# Backplane-4.net
KiCad netlist of a schematic drawn in EAGLE
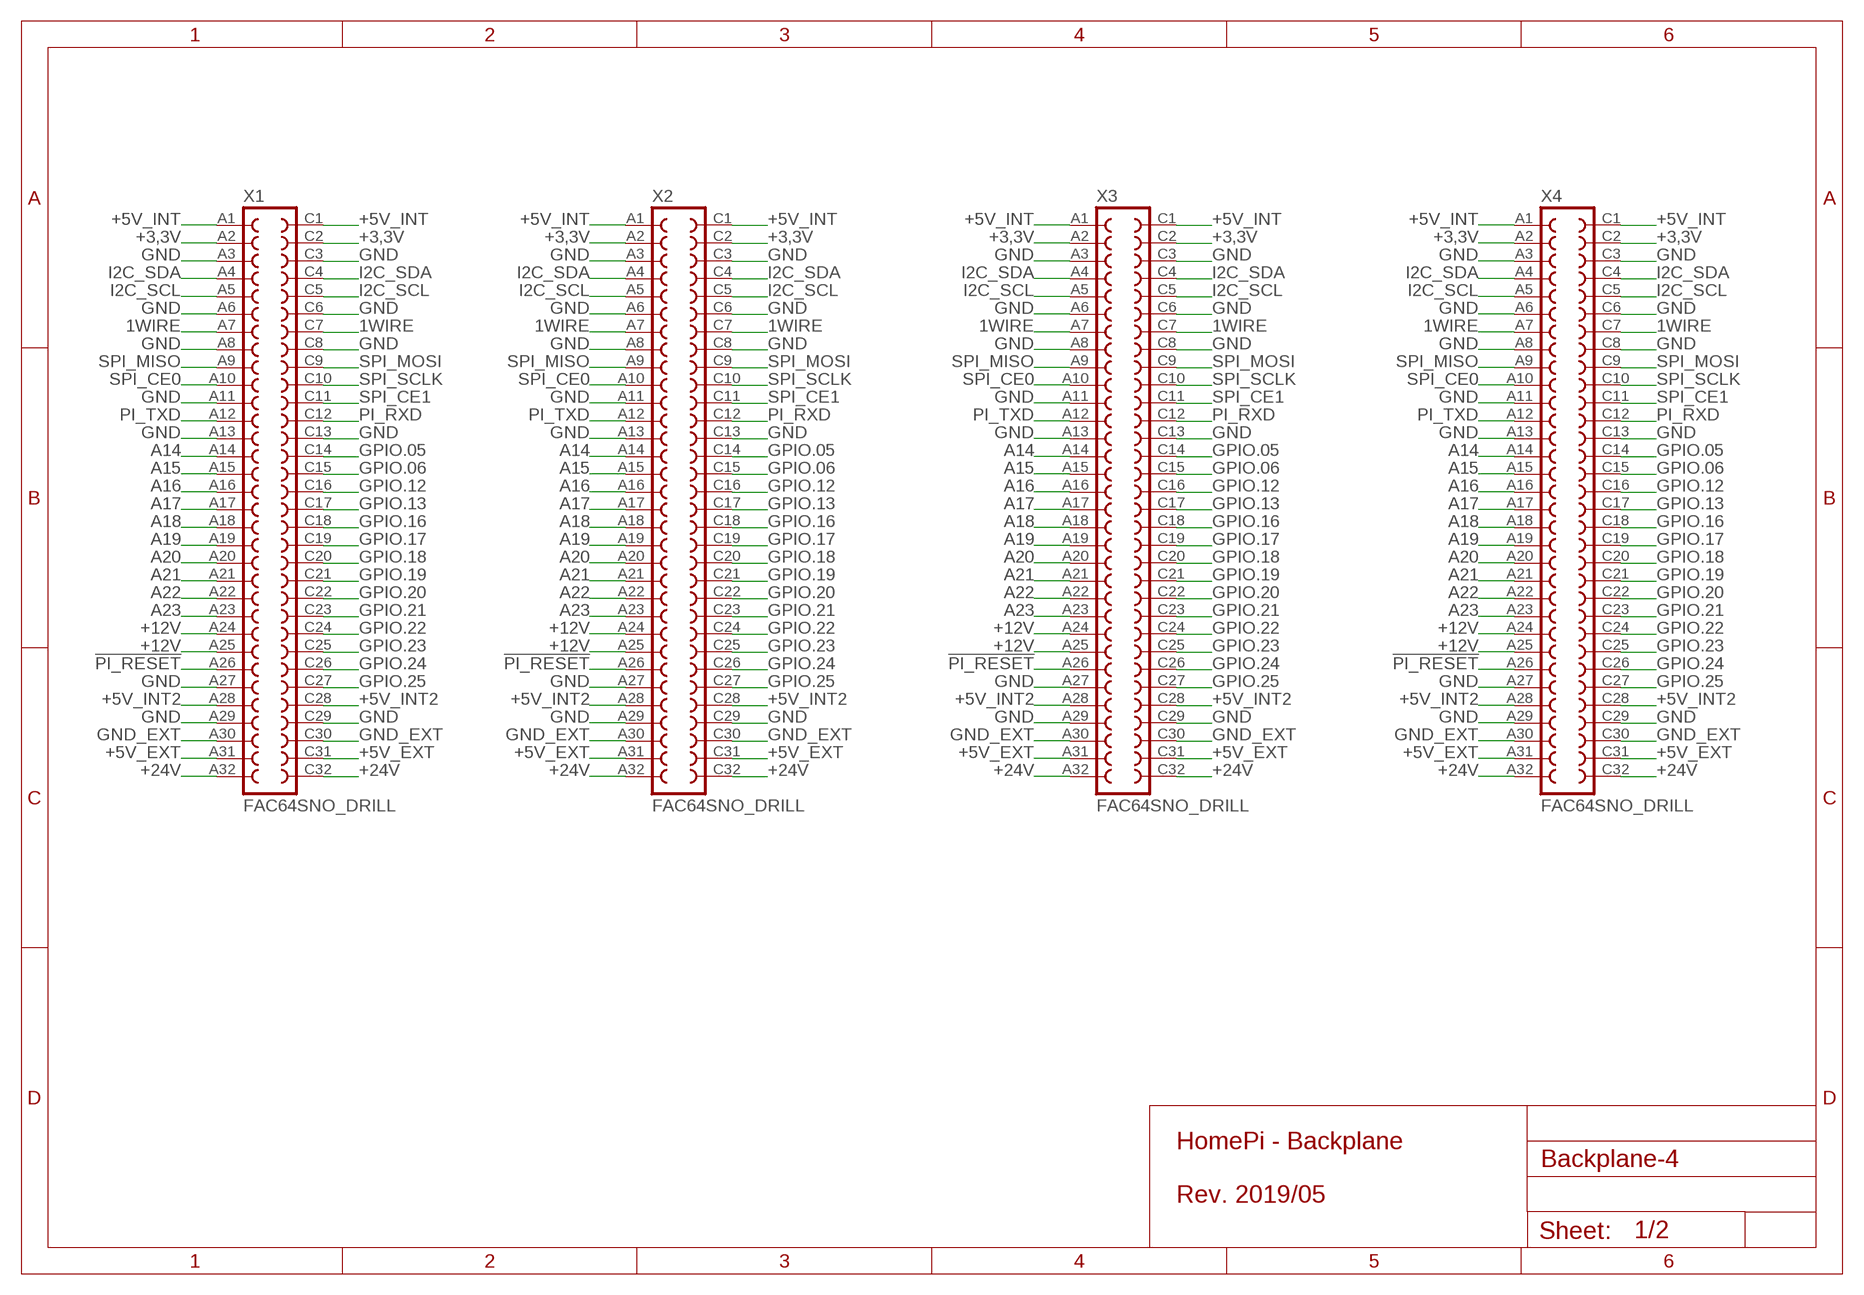
[diagram p0: schematic, sheet 1]
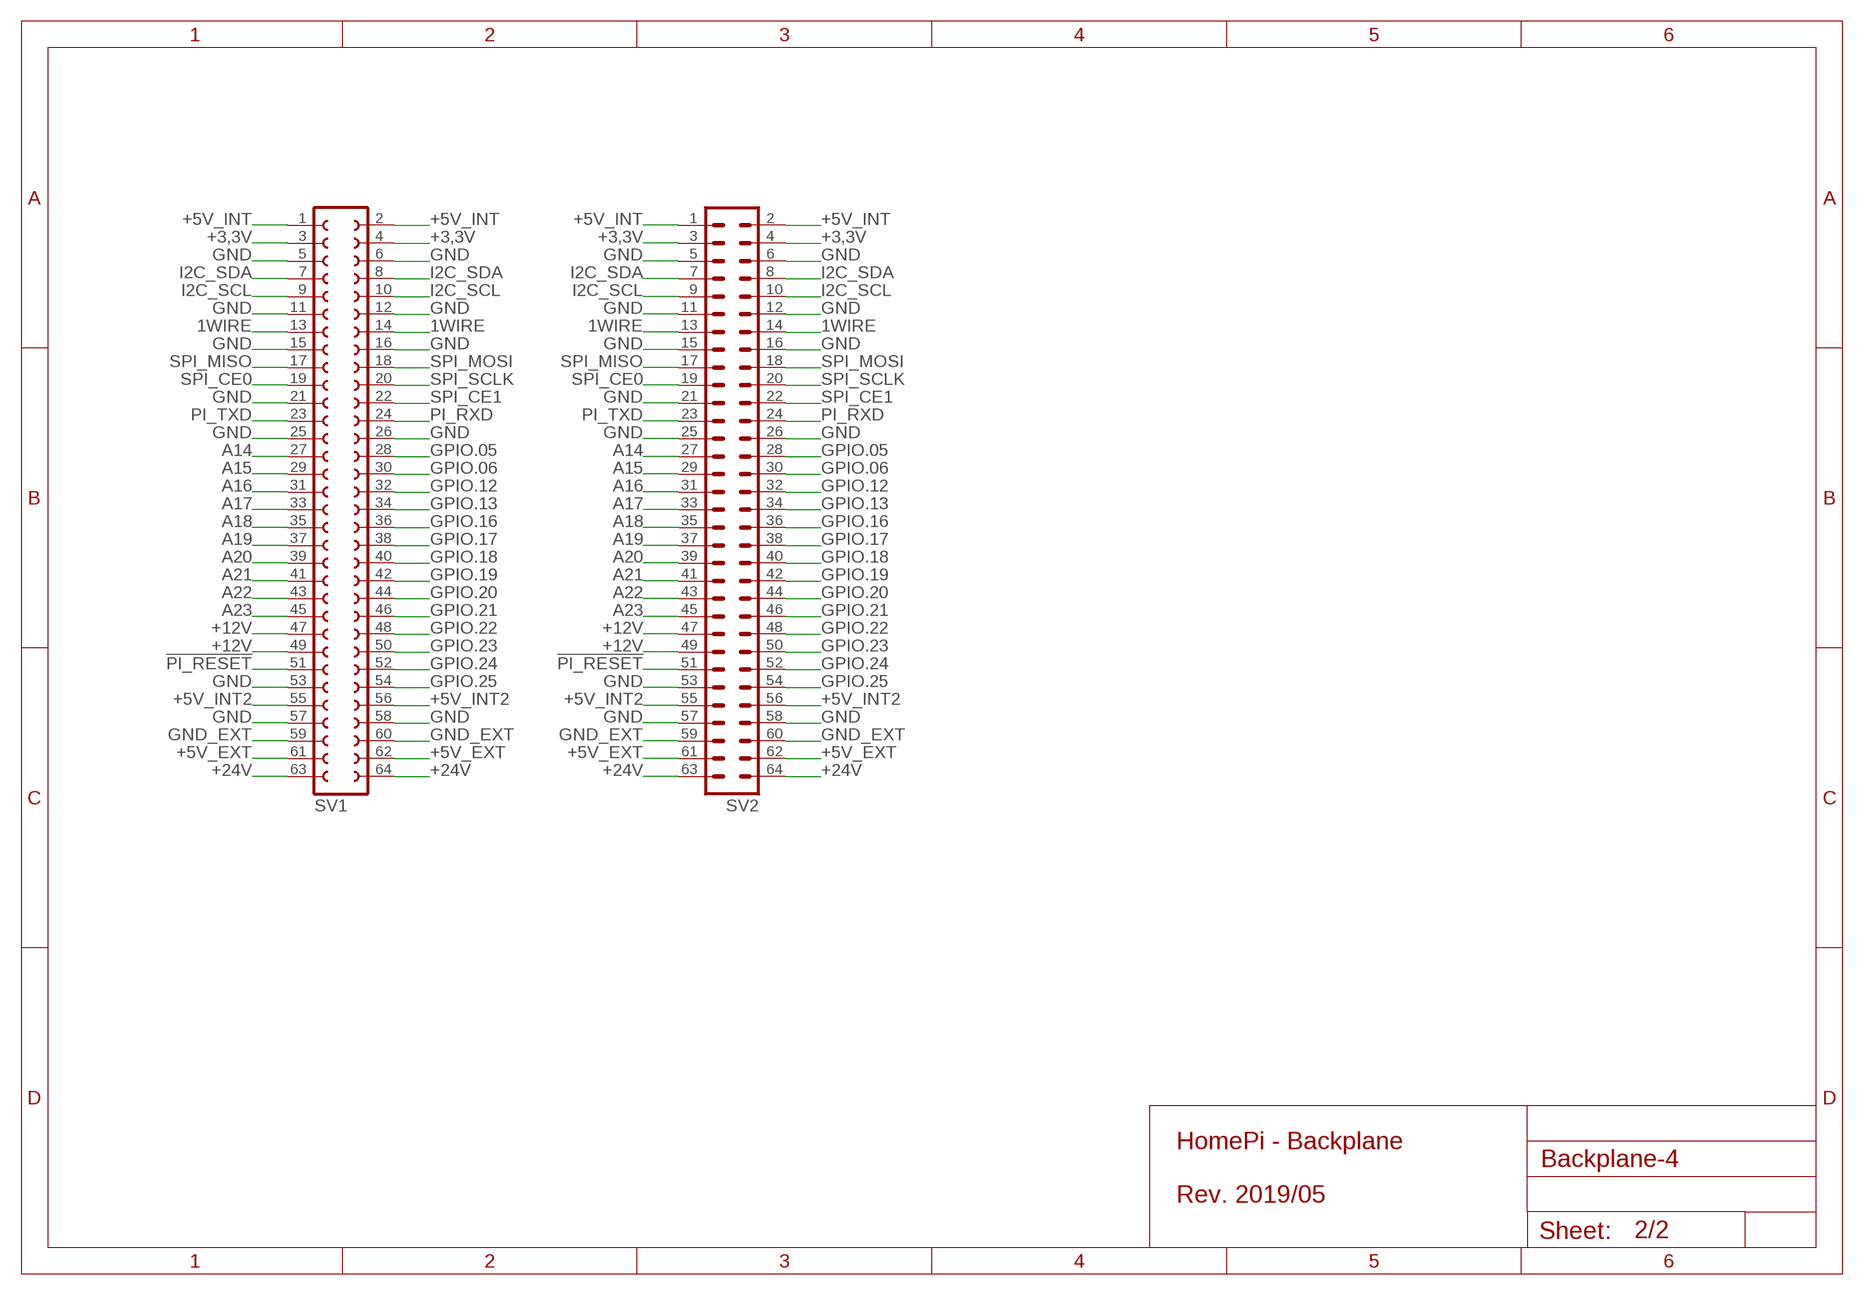
[diagram p1: schematic, sheet 2]

(export (version "E")
  (design (tool "Eeschema 10.0.6"))
  (components
    (comp (ref "X1")
      (value "FAC64SNO_DRILL")
      (footprint "eagle-import:FAC64S_NO_DRILL")
      (libsource (lib "eagle-import") (part "FAC64SNO_DRILL"))
    )
    (comp (ref "X2")
      (value "FAC64SNO_DRILL")
      (footprint "eagle-import:FAC64S_NO_DRILL")
      (libsource (lib "eagle-import") (part "FAC64SNO_DRILL"))
    )
    (comp (ref "X3")
      (value "FAC64SNO_DRILL")
      (footprint "eagle-import:FAC64S_NO_DRILL")
      (libsource (lib "eagle-import") (part "FAC64SNO_DRILL"))
    )
    (comp (ref "X4")
      (value "FAC64SNO_DRILL")
      (footprint "eagle-import:FAC64S_NO_DRILL")
      (libsource (lib "eagle-import") (part "FAC64SNO_DRILL"))
    )
    (comp (ref "SV1")
      (value "FE32-2W")
      (footprint "eagle-import:FE32-2W")
      (libsource (lib "eagle-import") (part "FE32-2W"))
    )
    (comp (ref "SV2")
      (value "MA32-2W")
      (footprint "eagle-import:MA32-2W")
      (libsource (lib "eagle-import") (part "MA32-2W"))
    )
  )
  (nets
    (net (code "1") (name "+3,3V") (class "Default")
      (node (ref "SV1") (pin "3") (pinfunction "3_3") (pintype "passive"))
      (node (ref "SV1") (pin "4") (pinfunction "4_4") (pintype "passive"))
      (node (ref "SV2") (pin "3") (pinfunction "3_3") (pintype "passive"))
      (node (ref "SV2") (pin "4") (pinfunction "4_4") (pintype "passive"))
      (node (ref "X1") (pin "A2") (pinfunction "A2_A2") (pintype "passive"))
      (node (ref "X1") (pin "C2") (pinfunction "C2_C2") (pintype "passive"))
      (node (ref "X2") (pin "A2") (pinfunction "A2_A2") (pintype "passive"))
      (node (ref "X2") (pin "C2") (pinfunction "C2_C2") (pintype "passive"))
      (node (ref "X3") (pin "A2") (pinfunction "A2_A2") (pintype "passive"))
      (node (ref "X3") (pin "C2") (pinfunction "C2_C2") (pintype "passive"))
      (node (ref "X4") (pin "A2") (pinfunction "A2_A2") (pintype "passive"))
      (node (ref "X4") (pin "C2") (pinfunction "C2_C2") (pintype "passive"))
    )
    (net (code "2") (name "+5V_EXT") (class "Default")
      (node (ref "SV1") (pin "61") (pinfunction "61_61") (pintype "passive"))
      (node (ref "SV1") (pin "62") (pinfunction "62_62") (pintype "passive"))
      (node (ref "SV2") (pin "61") (pinfunction "61_61") (pintype "passive"))
      (node (ref "SV2") (pin "62") (pinfunction "62_62") (pintype "passive"))
      (node (ref "X1") (pin "A31") (pinfunction "A31_A31") (pintype "passive"))
      (node (ref "X1") (pin "C31") (pinfunction "C31_C31") (pintype "passive"))
      (node (ref "X2") (pin "A31") (pinfunction "A31_A31") (pintype "passive"))
      (node (ref "X2") (pin "C31") (pinfunction "C31_C31") (pintype "passive"))
      (node (ref "X3") (pin "A31") (pinfunction "A31_A31") (pintype "passive"))
      (node (ref "X3") (pin "C31") (pinfunction "C31_C31") (pintype "passive"))
      (node (ref "X4") (pin "A31") (pinfunction "A31_A31") (pintype "passive"))
      (node (ref "X4") (pin "C31") (pinfunction "C31_C31") (pintype "passive"))
    )
    (net (code "3") (name "+5V_INT") (class "Default")
      (node (ref "SV1") (pin "1") (pinfunction "1_1") (pintype "passive"))
      (node (ref "SV1") (pin "2") (pinfunction "2_2") (pintype "passive"))
      (node (ref "SV2") (pin "1") (pinfunction "1_1") (pintype "passive"))
      (node (ref "SV2") (pin "2") (pinfunction "2_2") (pintype "passive"))
      (node (ref "X1") (pin "A1") (pinfunction "A1_A1") (pintype "passive"))
      (node (ref "X1") (pin "C1") (pinfunction "C1_C1") (pintype "passive"))
      (node (ref "X2") (pin "A1") (pinfunction "A1_A1") (pintype "passive"))
      (node (ref "X2") (pin "C1") (pinfunction "C1_C1") (pintype "passive"))
      (node (ref "X3") (pin "A1") (pinfunction "A1_A1") (pintype "passive"))
      (node (ref "X3") (pin "C1") (pinfunction "C1_C1") (pintype "passive"))
      (node (ref "X4") (pin "A1") (pinfunction "A1_A1") (pintype "passive"))
      (node (ref "X4") (pin "C1") (pinfunction "C1_C1") (pintype "passive"))
    )
    (net (code "4") (name "+5V_INT2") (class "Default")
      (node (ref "SV1") (pin "55") (pinfunction "55_55") (pintype "passive"))
      (node (ref "SV1") (pin "56") (pinfunction "56_56") (pintype "passive"))
      (node (ref "SV2") (pin "55") (pinfunction "55_55") (pintype "passive"))
      (node (ref "SV2") (pin "56") (pinfunction "56_56") (pintype "passive"))
      (node (ref "X1") (pin "A28") (pinfunction "A28_A28") (pintype "passive"))
      (node (ref "X1") (pin "C28") (pinfunction "C28_C28") (pintype "passive"))
      (node (ref "X2") (pin "A28") (pinfunction "A28_A28") (pintype "passive"))
      (node (ref "X2") (pin "C28") (pinfunction "C28_C28") (pintype "passive"))
      (node (ref "X3") (pin "A28") (pinfunction "A28_A28") (pintype "passive"))
      (node (ref "X3") (pin "C28") (pinfunction "C28_C28") (pintype "passive"))
      (node (ref "X4") (pin "A28") (pinfunction "A28_A28") (pintype "passive"))
      (node (ref "X4") (pin "C28") (pinfunction "C28_C28") (pintype "passive"))
    )
    (net (code "5") (name "+12V") (class "Default")
      (node (ref "SV1") (pin "47") (pinfunction "47_47") (pintype "passive"))
      (node (ref "SV1") (pin "49") (pinfunction "49_49") (pintype "passive"))
      (node (ref "SV2") (pin "47") (pinfunction "47_47") (pintype "passive"))
      (node (ref "SV2") (pin "49") (pinfunction "49_49") (pintype "passive"))
      (node (ref "X1") (pin "A24") (pinfunction "A24_A24") (pintype "passive"))
      (node (ref "X1") (pin "A25") (pinfunction "A25_A25") (pintype "passive"))
      (node (ref "X2") (pin "A24") (pinfunction "A24_A24") (pintype "passive"))
      (node (ref "X2") (pin "A25") (pinfunction "A25_A25") (pintype "passive"))
      (node (ref "X3") (pin "A24") (pinfunction "A24_A24") (pintype "passive"))
      (node (ref "X3") (pin "A25") (pinfunction "A25_A25") (pintype "passive"))
      (node (ref "X4") (pin "A24") (pinfunction "A24_A24") (pintype "passive"))
      (node (ref "X4") (pin "A25") (pinfunction "A25_A25") (pintype "passive"))
    )
    (net (code "6") (name "+24V") (class "Default")
      (node (ref "SV1") (pin "63") (pinfunction "63_63") (pintype "passive"))
      (node (ref "SV1") (pin "64") (pinfunction "64_64") (pintype "passive"))
      (node (ref "SV2") (pin "63") (pinfunction "63_63") (pintype "passive"))
      (node (ref "SV2") (pin "64") (pinfunction "64_64") (pintype "passive"))
      (node (ref "X1") (pin "A32") (pinfunction "A32_A32") (pintype "passive"))
      (node (ref "X1") (pin "C32") (pinfunction "C32_C32") (pintype "passive"))
      (node (ref "X2") (pin "A32") (pinfunction "A32_A32") (pintype "passive"))
      (node (ref "X2") (pin "C32") (pinfunction "C32_C32") (pintype "passive"))
      (node (ref "X3") (pin "A32") (pinfunction "A32_A32") (pintype "passive"))
      (node (ref "X3") (pin "C32") (pinfunction "C32_C32") (pintype "passive"))
      (node (ref "X4") (pin "A32") (pinfunction "A32_A32") (pintype "passive"))
      (node (ref "X4") (pin "C32") (pinfunction "C32_C32") (pintype "passive"))
    )
    (net (code "7") (name "1WIRE") (class "Default")
      (node (ref "SV1") (pin "13") (pinfunction "13_13") (pintype "passive"))
      (node (ref "SV1") (pin "14") (pinfunction "14_14") (pintype "passive"))
      (node (ref "SV2") (pin "13") (pinfunction "13_13") (pintype "passive"))
      (node (ref "SV2") (pin "14") (pinfunction "14_14") (pintype "passive"))
      (node (ref "X1") (pin "A7") (pinfunction "A7_A7") (pintype "passive"))
      (node (ref "X1") (pin "C7") (pinfunction "C7_C7") (pintype "passive"))
      (node (ref "X2") (pin "A7") (pinfunction "A7_A7") (pintype "passive"))
      (node (ref "X2") (pin "C7") (pinfunction "C7_C7") (pintype "passive"))
      (node (ref "X3") (pin "A7") (pinfunction "A7_A7") (pintype "passive"))
      (node (ref "X3") (pin "C7") (pinfunction "C7_C7") (pintype "passive"))
      (node (ref "X4") (pin "A7") (pinfunction "A7_A7") (pintype "passive"))
      (node (ref "X4") (pin "C7") (pinfunction "C7_C7") (pintype "passive"))
    )
    (net (code "8") (name "A14") (class "Default")
      (node (ref "SV1") (pin "27") (pinfunction "27_27") (pintype "passive"))
      (node (ref "SV2") (pin "27") (pinfunction "27_27") (pintype "passive"))
      (node (ref "X1") (pin "A14") (pinfunction "A14_A14") (pintype "passive"))
      (node (ref "X2") (pin "A14") (pinfunction "A14_A14") (pintype "passive"))
      (node (ref "X3") (pin "A14") (pinfunction "A14_A14") (pintype "passive"))
      (node (ref "X4") (pin "A14") (pinfunction "A14_A14") (pintype "passive"))
    )
    (net (code "9") (name "A15") (class "Default")
      (node (ref "SV1") (pin "29") (pinfunction "29_29") (pintype "passive"))
      (node (ref "SV2") (pin "29") (pinfunction "29_29") (pintype "passive"))
      (node (ref "X1") (pin "A15") (pinfunction "A15_A15") (pintype "passive"))
      (node (ref "X2") (pin "A15") (pinfunction "A15_A15") (pintype "passive"))
      (node (ref "X3") (pin "A15") (pinfunction "A15_A15") (pintype "passive"))
      (node (ref "X4") (pin "A15") (pinfunction "A15_A15") (pintype "passive"))
    )
    (net (code "10") (name "A16") (class "Default")
      (node (ref "SV1") (pin "31") (pinfunction "31_31") (pintype "passive"))
      (node (ref "SV2") (pin "31") (pinfunction "31_31") (pintype "passive"))
      (node (ref "X1") (pin "A16") (pinfunction "A16_A16") (pintype "passive"))
      (node (ref "X2") (pin "A16") (pinfunction "A16_A16") (pintype "passive"))
      (node (ref "X3") (pin "A16") (pinfunction "A16_A16") (pintype "passive"))
      (node (ref "X4") (pin "A16") (pinfunction "A16_A16") (pintype "passive"))
    )
    (net (code "11") (name "A17") (class "Default")
      (node (ref "SV1") (pin "33") (pinfunction "33_33") (pintype "passive"))
      (node (ref "SV2") (pin "33") (pinfunction "33_33") (pintype "passive"))
      (node (ref "X1") (pin "A17") (pinfunction "A17_A17") (pintype "passive"))
      (node (ref "X2") (pin "A17") (pinfunction "A17_A17") (pintype "passive"))
      (node (ref "X3") (pin "A17") (pinfunction "A17_A17") (pintype "passive"))
      (node (ref "X4") (pin "A17") (pinfunction "A17_A17") (pintype "passive"))
    )
    (net (code "12") (name "A18") (class "Default")
      (node (ref "SV1") (pin "35") (pinfunction "35_35") (pintype "passive"))
      (node (ref "SV2") (pin "35") (pinfunction "35_35") (pintype "passive"))
      (node (ref "X1") (pin "A18") (pinfunction "A18_A18") (pintype "passive"))
      (node (ref "X2") (pin "A18") (pinfunction "A18_A18") (pintype "passive"))
      (node (ref "X3") (pin "A18") (pinfunction "A18_A18") (pintype "passive"))
      (node (ref "X4") (pin "A18") (pinfunction "A18_A18") (pintype "passive"))
    )
    (net (code "13") (name "A19") (class "Default")
      (node (ref "SV1") (pin "37") (pinfunction "37_37") (pintype "passive"))
      (node (ref "SV2") (pin "37") (pinfunction "37_37") (pintype "passive"))
      (node (ref "X1") (pin "A19") (pinfunction "A19_A19") (pintype "passive"))
      (node (ref "X2") (pin "A19") (pinfunction "A19_A19") (pintype "passive"))
      (node (ref "X3") (pin "A19") (pinfunction "A19_A19") (pintype "passive"))
      (node (ref "X4") (pin "A19") (pinfunction "A19_A19") (pintype "passive"))
    )
    (net (code "14") (name "A20") (class "Default")
      (node (ref "SV1") (pin "39") (pinfunction "39_39") (pintype "passive"))
      (node (ref "SV2") (pin "39") (pinfunction "39_39") (pintype "passive"))
      (node (ref "X1") (pin "A20") (pinfunction "A20_A20") (pintype "passive"))
      (node (ref "X2") (pin "A20") (pinfunction "A20_A20") (pintype "passive"))
      (node (ref "X3") (pin "A20") (pinfunction "A20_A20") (pintype "passive"))
      (node (ref "X4") (pin "A20") (pinfunction "A20_A20") (pintype "passive"))
    )
    (net (code "15") (name "A21") (class "Default")
      (node (ref "SV1") (pin "41") (pinfunction "41_41") (pintype "passive"))
      (node (ref "SV2") (pin "41") (pinfunction "41_41") (pintype "passive"))
      (node (ref "X1") (pin "A21") (pinfunction "A21_A21") (pintype "passive"))
      (node (ref "X2") (pin "A21") (pinfunction "A21_A21") (pintype "passive"))
      (node (ref "X3") (pin "A21") (pinfunction "A21_A21") (pintype "passive"))
      (node (ref "X4") (pin "A21") (pinfunction "A21_A21") (pintype "passive"))
    )
    (net (code "16") (name "A22") (class "Default")
      (node (ref "SV1") (pin "43") (pinfunction "43_43") (pintype "passive"))
      (node (ref "SV2") (pin "43") (pinfunction "43_43") (pintype "passive"))
      (node (ref "X1") (pin "A22") (pinfunction "A22_A22") (pintype "passive"))
      (node (ref "X2") (pin "A22") (pinfunction "A22_A22") (pintype "passive"))
      (node (ref "X3") (pin "A22") (pinfunction "A22_A22") (pintype "passive"))
      (node (ref "X4") (pin "A22") (pinfunction "A22_A22") (pintype "passive"))
    )
    (net (code "17") (name "A23") (class "Default")
      (node (ref "SV1") (pin "45") (pinfunction "45_45") (pintype "passive"))
      (node (ref "SV2") (pin "45") (pinfunction "45_45") (pintype "passive"))
      (node (ref "X1") (pin "A23") (pinfunction "A23_A23") (pintype "passive"))
      (node (ref "X2") (pin "A23") (pinfunction "A23_A23") (pintype "passive"))
      (node (ref "X3") (pin "A23") (pinfunction "A23_A23") (pintype "passive"))
      (node (ref "X4") (pin "A23") (pinfunction "A23_A23") (pintype "passive"))
    )
    (net (code "18") (name "GND") (class "Default")
      (node (ref "SV1") (pin "11") (pinfunction "11_11") (pintype "passive"))
      (node (ref "SV1") (pin "12") (pinfunction "12_12") (pintype "passive"))
      (node (ref "SV1") (pin "15") (pinfunction "15_15") (pintype "passive"))
      (node (ref "SV1") (pin "16") (pinfunction "16_16") (pintype "passive"))
      (node (ref "SV1") (pin "21") (pinfunction "21_21") (pintype "passive"))
      (node (ref "SV1") (pin "25") (pinfunction "25_25") (pintype "passive"))
      (node (ref "SV1") (pin "26") (pinfunction "26_26") (pintype "passive"))
      (node (ref "SV1") (pin "5") (pinfunction "5_5") (pintype "passive"))
      (node (ref "SV1") (pin "53") (pinfunction "53_53") (pintype "passive"))
      (node (ref "SV1") (pin "57") (pinfunction "57_57") (pintype "passive"))
      (node (ref "SV1") (pin "58") (pinfunction "58_58") (pintype "passive"))
      (node (ref "SV1") (pin "6") (pinfunction "6_6") (pintype "passive"))
      (node (ref "SV2") (pin "11") (pinfunction "11_11") (pintype "passive"))
      (node (ref "SV2") (pin "12") (pinfunction "12_12") (pintype "passive"))
      (node (ref "SV2") (pin "15") (pinfunction "15_15") (pintype "passive"))
      (node (ref "SV2") (pin "16") (pinfunction "16_16") (pintype "passive"))
      (node (ref "SV2") (pin "21") (pinfunction "21_21") (pintype "passive"))
      (node (ref "SV2") (pin "25") (pinfunction "25_25") (pintype "passive"))
      (node (ref "SV2") (pin "26") (pinfunction "26_26") (pintype "passive"))
      (node (ref "SV2") (pin "5") (pinfunction "5_5") (pintype "passive"))
      (node (ref "SV2") (pin "53") (pinfunction "53_53") (pintype "passive"))
      (node (ref "SV2") (pin "57") (pinfunction "57_57") (pintype "passive"))
      (node (ref "SV2") (pin "58") (pinfunction "58_58") (pintype "passive"))
      (node (ref "SV2") (pin "6") (pinfunction "6_6") (pintype "passive"))
      (node (ref "X1") (pin "A11") (pinfunction "A11_A11") (pintype "passive"))
      (node (ref "X1") (pin "A13") (pinfunction "A13_A13") (pintype "passive"))
      (node (ref "X1") (pin "A27") (pinfunction "A27_A27") (pintype "passive"))
      (node (ref "X1") (pin "A29") (pinfunction "A29_A29") (pintype "passive"))
      (node (ref "X1") (pin "A3") (pinfunction "A3_A3") (pintype "passive"))
      (node (ref "X1") (pin "A6") (pinfunction "A6_A6") (pintype "passive"))
      (node (ref "X1") (pin "A8") (pinfunction "A8_A8") (pintype "passive"))
      (node (ref "X1") (pin "C13") (pinfunction "C13_C13") (pintype "passive"))
      (node (ref "X1") (pin "C29") (pinfunction "C29_C29") (pintype "passive"))
      (node (ref "X1") (pin "C3") (pinfunction "C3_C3") (pintype "passive"))
      (node (ref "X1") (pin "C6") (pinfunction "C6_C6") (pintype "passive"))
      (node (ref "X1") (pin "C8") (pinfunction "C8_C8") (pintype "passive"))
      (node (ref "X2") (pin "A11") (pinfunction "A11_A11") (pintype "passive"))
      (node (ref "X2") (pin "A13") (pinfunction "A13_A13") (pintype "passive"))
      (node (ref "X2") (pin "A27") (pinfunction "A27_A27") (pintype "passive"))
      (node (ref "X2") (pin "A29") (pinfunction "A29_A29") (pintype "passive"))
      (node (ref "X2") (pin "A3") (pinfunction "A3_A3") (pintype "passive"))
      (node (ref "X2") (pin "A6") (pinfunction "A6_A6") (pintype "passive"))
      (node (ref "X2") (pin "A8") (pinfunction "A8_A8") (pintype "passive"))
      (node (ref "X2") (pin "C13") (pinfunction "C13_C13") (pintype "passive"))
      (node (ref "X2") (pin "C29") (pinfunction "C29_C29") (pintype "passive"))
      (node (ref "X2") (pin "C3") (pinfunction "C3_C3") (pintype "passive"))
      (node (ref "X2") (pin "C6") (pinfunction "C6_C6") (pintype "passive"))
      (node (ref "X2") (pin "C8") (pinfunction "C8_C8") (pintype "passive"))
      (node (ref "X3") (pin "A11") (pinfunction "A11_A11") (pintype "passive"))
      (node (ref "X3") (pin "A13") (pinfunction "A13_A13") (pintype "passive"))
      (node (ref "X3") (pin "A27") (pinfunction "A27_A27") (pintype "passive"))
      (node (ref "X3") (pin "A29") (pinfunction "A29_A29") (pintype "passive"))
      (node (ref "X3") (pin "A3") (pinfunction "A3_A3") (pintype "passive"))
      (node (ref "X3") (pin "A6") (pinfunction "A6_A6") (pintype "passive"))
      (node (ref "X3") (pin "A8") (pinfunction "A8_A8") (pintype "passive"))
      (node (ref "X3") (pin "C13") (pinfunction "C13_C13") (pintype "passive"))
      (node (ref "X3") (pin "C29") (pinfunction "C29_C29") (pintype "passive"))
      (node (ref "X3") (pin "C3") (pinfunction "C3_C3") (pintype "passive"))
      (node (ref "X3") (pin "C6") (pinfunction "C6_C6") (pintype "passive"))
      (node (ref "X3") (pin "C8") (pinfunction "C8_C8") (pintype "passive"))
      (node (ref "X4") (pin "A11") (pinfunction "A11_A11") (pintype "passive"))
      (node (ref "X4") (pin "A13") (pinfunction "A13_A13") (pintype "passive"))
      (node (ref "X4") (pin "A27") (pinfunction "A27_A27") (pintype "passive"))
      (node (ref "X4") (pin "A29") (pinfunction "A29_A29") (pintype "passive"))
      (node (ref "X4") (pin "A3") (pinfunction "A3_A3") (pintype "passive"))
      (node (ref "X4") (pin "A6") (pinfunction "A6_A6") (pintype "passive"))
      (node (ref "X4") (pin "A8") (pinfunction "A8_A8") (pintype "passive"))
      (node (ref "X4") (pin "C13") (pinfunction "C13_C13") (pintype "passive"))
      (node (ref "X4") (pin "C29") (pinfunction "C29_C29") (pintype "passive"))
      (node (ref "X4") (pin "C3") (pinfunction "C3_C3") (pintype "passive"))
      (node (ref "X4") (pin "C6") (pinfunction "C6_C6") (pintype "passive"))
      (node (ref "X4") (pin "C8") (pinfunction "C8_C8") (pintype "passive"))
    )
    (net (code "19") (name "GND_EXT") (class "Default")
      (node (ref "SV1") (pin "59") (pinfunction "59_59") (pintype "passive"))
      (node (ref "SV1") (pin "60") (pinfunction "60_60") (pintype "passive"))
      (node (ref "SV2") (pin "59") (pinfunction "59_59") (pintype "passive"))
      (node (ref "SV2") (pin "60") (pinfunction "60_60") (pintype "passive"))
      (node (ref "X1") (pin "A30") (pinfunction "A30_A30") (pintype "passive"))
      (node (ref "X1") (pin "C30") (pinfunction "C30_C30") (pintype "passive"))
      (node (ref "X2") (pin "A30") (pinfunction "A30_A30") (pintype "passive"))
      (node (ref "X2") (pin "C30") (pinfunction "C30_C30") (pintype "passive"))
      (node (ref "X3") (pin "A30") (pinfunction "A30_A30") (pintype "passive"))
      (node (ref "X3") (pin "C30") (pinfunction "C30_C30") (pintype "passive"))
      (node (ref "X4") (pin "A30") (pinfunction "A30_A30") (pintype "passive"))
      (node (ref "X4") (pin "C30") (pinfunction "C30_C30") (pintype "passive"))
    )
    (net (code "20") (name "GPIO.05") (class "Default")
      (node (ref "SV1") (pin "28") (pinfunction "28_28") (pintype "passive"))
      (node (ref "SV2") (pin "28") (pinfunction "28_28") (pintype "passive"))
      (node (ref "X1") (pin "C14") (pinfunction "C14_C14") (pintype "passive"))
      (node (ref "X2") (pin "C14") (pinfunction "C14_C14") (pintype "passive"))
      (node (ref "X3") (pin "C14") (pinfunction "C14_C14") (pintype "passive"))
      (node (ref "X4") (pin "C14") (pinfunction "C14_C14") (pintype "passive"))
    )
    (net (code "21") (name "GPIO.06") (class "Default")
      (node (ref "SV1") (pin "30") (pinfunction "30_30") (pintype "passive"))
      (node (ref "SV2") (pin "30") (pinfunction "30_30") (pintype "passive"))
      (node (ref "X1") (pin "C15") (pinfunction "C15_C15") (pintype "passive"))
      (node (ref "X2") (pin "C15") (pinfunction "C15_C15") (pintype "passive"))
      (node (ref "X3") (pin "C15") (pinfunction "C15_C15") (pintype "passive"))
      (node (ref "X4") (pin "C15") (pinfunction "C15_C15") (pintype "passive"))
    )
    (net (code "22") (name "GPIO.12") (class "Default")
      (node (ref "SV1") (pin "32") (pinfunction "32_32") (pintype "passive"))
      (node (ref "SV2") (pin "32") (pinfunction "32_32") (pintype "passive"))
      (node (ref "X1") (pin "C16") (pinfunction "C16_C16") (pintype "passive"))
      (node (ref "X2") (pin "C16") (pinfunction "C16_C16") (pintype "passive"))
      (node (ref "X3") (pin "C16") (pinfunction "C16_C16") (pintype "passive"))
      (node (ref "X4") (pin "C16") (pinfunction "C16_C16") (pintype "passive"))
    )
    (net (code "23") (name "GPIO.13") (class "Default")
      (node (ref "SV1") (pin "34") (pinfunction "34_34") (pintype "passive"))
      (node (ref "SV2") (pin "34") (pinfunction "34_34") (pintype "passive"))
      (node (ref "X1") (pin "C17") (pinfunction "C17_C17") (pintype "passive"))
      (node (ref "X2") (pin "C17") (pinfunction "C17_C17") (pintype "passive"))
      (node (ref "X3") (pin "C17") (pinfunction "C17_C17") (pintype "passive"))
      (node (ref "X4") (pin "C17") (pinfunction "C17_C17") (pintype "passive"))
    )
    (net (code "24") (name "GPIO.16") (class "Default")
      (node (ref "SV1") (pin "36") (pinfunction "36_36") (pintype "passive"))
      (node (ref "SV2") (pin "36") (pinfunction "36_36") (pintype "passive"))
      (node (ref "X1") (pin "C18") (pinfunction "C18_C18") (pintype "passive"))
      (node (ref "X2") (pin "C18") (pinfunction "C18_C18") (pintype "passive"))
      (node (ref "X3") (pin "C18") (pinfunction "C18_C18") (pintype "passive"))
      (node (ref "X4") (pin "C18") (pinfunction "C18_C18") (pintype "passive"))
    )
    (net (code "25") (name "GPIO.17") (class "Default")
      (node (ref "SV1") (pin "38") (pinfunction "38_38") (pintype "passive"))
      (node (ref "SV2") (pin "38") (pinfunction "38_38") (pintype "passive"))
      (node (ref "X1") (pin "C19") (pinfunction "C19_C19") (pintype "passive"))
      (node (ref "X2") (pin "C19") (pinfunction "C19_C19") (pintype "passive"))
      (node (ref "X3") (pin "C19") (pinfunction "C19_C19") (pintype "passive"))
      (node (ref "X4") (pin "C19") (pinfunction "C19_C19") (pintype "passive"))
    )
    (net (code "26") (name "GPIO.18") (class "Default")
      (node (ref "SV1") (pin "40") (pinfunction "40_40") (pintype "passive"))
      (node (ref "SV2") (pin "40") (pinfunction "40_40") (pintype "passive"))
      (node (ref "X1") (pin "C20") (pinfunction "C20_C20") (pintype "passive"))
      (node (ref "X2") (pin "C20") (pinfunction "C20_C20") (pintype "passive"))
      (node (ref "X3") (pin "C20") (pinfunction "C20_C20") (pintype "passive"))
      (node (ref "X4") (pin "C20") (pinfunction "C20_C20") (pintype "passive"))
    )
    (net (code "27") (name "GPIO.19") (class "Default")
      (node (ref "SV1") (pin "42") (pinfunction "42_42") (pintype "passive"))
      (node (ref "SV2") (pin "42") (pinfunction "42_42") (pintype "passive"))
      (node (ref "X1") (pin "C21") (pinfunction "C21_C21") (pintype "passive"))
      (node (ref "X2") (pin "C21") (pinfunction "C21_C21") (pintype "passive"))
      (node (ref "X3") (pin "C21") (pinfunction "C21_C21") (pintype "passive"))
      (node (ref "X4") (pin "C21") (pinfunction "C21_C21") (pintype "passive"))
    )
    (net (code "28") (name "GPIO.20") (class "Default")
      (node (ref "SV1") (pin "44") (pinfunction "44_44") (pintype "passive"))
      (node (ref "SV2") (pin "44") (pinfunction "44_44") (pintype "passive"))
      (node (ref "X1") (pin "C22") (pinfunction "C22_C22") (pintype "passive"))
      (node (ref "X2") (pin "C22") (pinfunction "C22_C22") (pintype "passive"))
      (node (ref "X3") (pin "C22") (pinfunction "C22_C22") (pintype "passive"))
      (node (ref "X4") (pin "C22") (pinfunction "C22_C22") (pintype "passive"))
    )
    (net (code "29") (name "GPIO.21") (class "Default")
      (node (ref "SV1") (pin "46") (pinfunction "46_46") (pintype "passive"))
      (node (ref "SV2") (pin "46") (pinfunction "46_46") (pintype "passive"))
      (node (ref "X1") (pin "C23") (pinfunction "C23_C23") (pintype "passive"))
      (node (ref "X2") (pin "C23") (pinfunction "C23_C23") (pintype "passive"))
      (node (ref "X3") (pin "C23") (pinfunction "C23_C23") (pintype "passive"))
      (node (ref "X4") (pin "C23") (pinfunction "C23_C23") (pintype "passive"))
    )
    (net (code "30") (name "GPIO.22") (class "Default")
      (node (ref "SV1") (pin "48") (pinfunction "48_48") (pintype "passive"))
      (node (ref "SV2") (pin "48") (pinfunction "48_48") (pintype "passive"))
      (node (ref "X1") (pin "C24") (pinfunction "C24_C24") (pintype "passive"))
      (node (ref "X2") (pin "C24") (pinfunction "C24_C24") (pintype "passive"))
      (node (ref "X3") (pin "C24") (pinfunction "C24_C24") (pintype "passive"))
      (node (ref "X4") (pin "C24") (pinfunction "C24_C24") (pintype "passive"))
    )
    (net (code "31") (name "GPIO.23") (class "Default")
      (node (ref "SV1") (pin "50") (pinfunction "50_50") (pintype "passive"))
      (node (ref "SV2") (pin "50") (pinfunction "50_50") (pintype "passive"))
      (node (ref "X1") (pin "C25") (pinfunction "C25_C25") (pintype "passive"))
      (node (ref "X2") (pin "C25") (pinfunction "C25_C25") (pintype "passive"))
      (node (ref "X3") (pin "C25") (pinfunction "C25_C25") (pintype "passive"))
      (node (ref "X4") (pin "C25") (pinfunction "C25_C25") (pintype "passive"))
    )
    (net (code "32") (name "GPIO.24") (class "Default")
      (node (ref "SV1") (pin "52") (pinfunction "52_52") (pintype "passive"))
      (node (ref "SV2") (pin "52") (pinfunction "52_52") (pintype "passive"))
      (node (ref "X1") (pin "C26") (pinfunction "C26_C26") (pintype "passive"))
      (node (ref "X2") (pin "C26") (pinfunction "C26_C26") (pintype "passive"))
      (node (ref "X3") (pin "C26") (pinfunction "C26_C26") (pintype "passive"))
      (node (ref "X4") (pin "C26") (pinfunction "C26_C26") (pintype "passive"))
    )
    (net (code "33") (name "GPIO.25") (class "Default")
      (node (ref "SV1") (pin "54") (pinfunction "54_54") (pintype "passive"))
      (node (ref "SV2") (pin "54") (pinfunction "54_54") (pintype "passive"))
      (node (ref "X1") (pin "C27") (pinfunction "C27_C27") (pintype "passive"))
      (node (ref "X2") (pin "C27") (pinfunction "C27_C27") (pintype "passive"))
      (node (ref "X3") (pin "C27") (pinfunction "C27_C27") (pintype "passive"))
      (node (ref "X4") (pin "C27") (pinfunction "C27_C27") (pintype "passive"))
    )
    (net (code "34") (name "I2C_SCL") (class "Default")
      (node (ref "SV1") (pin "10") (pinfunction "10_10") (pintype "passive"))
      (node (ref "SV1") (pin "9") (pinfunction "9_9") (pintype "passive"))
      (node (ref "SV2") (pin "10") (pinfunction "10_10") (pintype "passive"))
      (node (ref "SV2") (pin "9") (pinfunction "9_9") (pintype "passive"))
      (node (ref "X1") (pin "A5") (pinfunction "A5_A5") (pintype "passive"))
      (node (ref "X1") (pin "C5") (pinfunction "C5_C5") (pintype "passive"))
      (node (ref "X2") (pin "A5") (pinfunction "A5_A5") (pintype "passive"))
      (node (ref "X2") (pin "C5") (pinfunction "C5_C5") (pintype "passive"))
      (node (ref "X3") (pin "A5") (pinfunction "A5_A5") (pintype "passive"))
      (node (ref "X3") (pin "C5") (pinfunction "C5_C5") (pintype "passive"))
      (node (ref "X4") (pin "A5") (pinfunction "A5_A5") (pintype "passive"))
      (node (ref "X4") (pin "C5") (pinfunction "C5_C5") (pintype "passive"))
    )
    (net (code "35") (name "I2C_SDA") (class "Default")
      (node (ref "SV1") (pin "7") (pinfunction "7_7") (pintype "passive"))
      (node (ref "SV1") (pin "8") (pinfunction "8_8") (pintype "passive"))
      (node (ref "SV2") (pin "7") (pinfunction "7_7") (pintype "passive"))
      (node (ref "SV2") (pin "8") (pinfunction "8_8") (pintype "passive"))
      (node (ref "X1") (pin "A4") (pinfunction "A4_A4") (pintype "passive"))
      (node (ref "X1") (pin "C4") (pinfunction "C4_C4") (pintype "passive"))
      (node (ref "X2") (pin "A4") (pinfunction "A4_A4") (pintype "passive"))
      (node (ref "X2") (pin "C4") (pinfunction "C4_C4") (pintype "passive"))
      (node (ref "X3") (pin "A4") (pinfunction "A4_A4") (pintype "passive"))
      (node (ref "X3") (pin "C4") (pinfunction "C4_C4") (pintype "passive"))
      (node (ref "X4") (pin "A4") (pinfunction "A4_A4") (pintype "passive"))
      (node (ref "X4") (pin "C4") (pinfunction "C4_C4") (pintype "passive"))
    )
    (net (code "36") (name "PI_RXD") (class "Default")
      (node (ref "SV1") (pin "24") (pinfunction "24_24") (pintype "passive"))
      (node (ref "SV2") (pin "24") (pinfunction "24_24") (pintype "passive"))
      (node (ref "X1") (pin "C12") (pinfunction "C12_C12") (pintype "passive"))
      (node (ref "X2") (pin "C12") (pinfunction "C12_C12") (pintype "passive"))
      (node (ref "X3") (pin "C12") (pinfunction "C12_C12") (pintype "passive"))
      (node (ref "X4") (pin "C12") (pinfunction "C12_C12") (pintype "passive"))
    )
    (net (code "37") (name "PI_TXD") (class "Default")
      (node (ref "SV1") (pin "23") (pinfunction "23_23") (pintype "passive"))
      (node (ref "SV2") (pin "23") (pinfunction "23_23") (pintype "passive"))
      (node (ref "X1") (pin "A12") (pinfunction "A12_A12") (pintype "passive"))
      (node (ref "X2") (pin "A12") (pinfunction "A12_A12") (pintype "passive"))
      (node (ref "X3") (pin "A12") (pinfunction "A12_A12") (pintype "passive"))
      (node (ref "X4") (pin "A12") (pinfunction "A12_A12") (pintype "passive"))
    )
    (net (code "38") (name "SPI_CE0") (class "Default")
      (node (ref "SV1") (pin "19") (pinfunction "19_19") (pintype "passive"))
      (node (ref "SV2") (pin "19") (pinfunction "19_19") (pintype "passive"))
      (node (ref "X1") (pin "A10") (pinfunction "A10_A10") (pintype "passive"))
      (node (ref "X2") (pin "A10") (pinfunction "A10_A10") (pintype "passive"))
      (node (ref "X3") (pin "A10") (pinfunction "A10_A10") (pintype "passive"))
      (node (ref "X4") (pin "A10") (pinfunction "A10_A10") (pintype "passive"))
    )
    (net (code "39") (name "SPI_CE1") (class "Default")
      (node (ref "SV1") (pin "22") (pinfunction "22_22") (pintype "passive"))
      (node (ref "SV2") (pin "22") (pinfunction "22_22") (pintype "passive"))
      (node (ref "X1") (pin "C11") (pinfunction "C11_C11") (pintype "passive"))
      (node (ref "X2") (pin "C11") (pinfunction "C11_C11") (pintype "passive"))
      (node (ref "X3") (pin "C11") (pinfunction "C11_C11") (pintype "passive"))
      (node (ref "X4") (pin "C11") (pinfunction "C11_C11") (pintype "passive"))
    )
    (net (code "40") (name "SPI_MISO") (class "Default")
      (node (ref "SV1") (pin "17") (pinfunction "17_17") (pintype "passive"))
      (node (ref "SV2") (pin "17") (pinfunction "17_17") (pintype "passive"))
      (node (ref "X1") (pin "A9") (pinfunction "A9_A9") (pintype "passive"))
      (node (ref "X2") (pin "A9") (pinfunction "A9_A9") (pintype "passive"))
      (node (ref "X3") (pin "A9") (pinfunction "A9_A9") (pintype "passive"))
      (node (ref "X4") (pin "A9") (pinfunction "A9_A9") (pintype "passive"))
    )
    (net (code "41") (name "SPI_MOSI") (class "Default")
      (node (ref "SV1") (pin "18") (pinfunction "18_18") (pintype "passive"))
      (node (ref "SV2") (pin "18") (pinfunction "18_18") (pintype "passive"))
      (node (ref "X1") (pin "C9") (pinfunction "C9_C9") (pintype "passive"))
      (node (ref "X2") (pin "C9") (pinfunction "C9_C9") (pintype "passive"))
      (node (ref "X3") (pin "C9") (pinfunction "C9_C9") (pintype "passive"))
      (node (ref "X4") (pin "C9") (pinfunction "C9_C9") (pintype "passive"))
    )
    (net (code "42") (name "SPI_SCLK") (class "Default")
      (node (ref "SV1") (pin "20") (pinfunction "20_20") (pintype "passive"))
      (node (ref "SV2") (pin "20") (pinfunction "20_20") (pintype "passive"))
      (node (ref "X1") (pin "C10") (pinfunction "C10_C10") (pintype "passive"))
      (node (ref "X2") (pin "C10") (pinfunction "C10_C10") (pintype "passive"))
      (node (ref "X3") (pin "C10") (pinfunction "C10_C10") (pintype "passive"))
      (node (ref "X4") (pin "C10") (pinfunction "C10_C10") (pintype "passive"))
    )
    (net (code "43") (name "~{PI_RESET}") (class "Default")
      (node (ref "SV1") (pin "51") (pinfunction "51_51") (pintype "passive"))
      (node (ref "SV2") (pin "51") (pinfunction "51_51") (pintype "passive"))
      (node (ref "X1") (pin "A26") (pinfunction "A26_A26") (pintype "passive"))
      (node (ref "X2") (pin "A26") (pinfunction "A26_A26") (pintype "passive"))
      (node (ref "X3") (pin "A26") (pinfunction "A26_A26") (pintype "passive"))
      (node (ref "X4") (pin "A26") (pinfunction "A26_A26") (pintype "passive"))
    )
  )
)
